# Teensy3_6Breakout.net
KiCad netlist of a schematic drawn in EAGLE
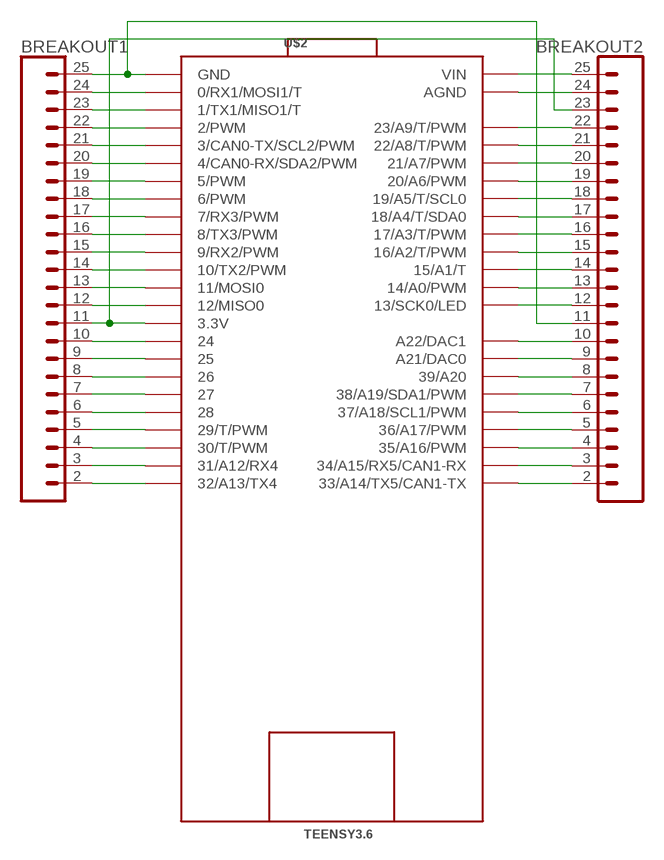
[diagram p0: schematic, sheet 1]

(export (version "E")
  (design (tool "Eeschema 10.0.6"))
  (components
    (comp (ref "BREAKOUT1")
      (value "CONN_24LONGPADS")
      (footprint "eagle-import:1X24_LONGPADS")
      (libsource (lib "eagle-import") (part "CONN_24LONGPADS"))
    )
    (comp (ref "BREAKOUT2")
      (value "CONN_24LONGPADS")
      (footprint "eagle-import:1X24_LONGPADS")
      (libsource (lib "eagle-import") (part "CONN_24LONGPADS"))
    )
    (comp (ref "U$2")
      (value "TEENSY3.6")
      (footprint "eagle-import:TEENSY3.6")
      (libsource (lib "eagle-import") (part "TEENSY3.6"))
    )
  )
  (nets
    (net (code "1") (name "Net-(BREAKOUT1-Pad6)") (class "Default")
      (node (ref "BREAKOUT1") (pin "6") (pinfunction "6_6") (pintype "passive"))
      (node (ref "U$2") (pin "28") (pinfunction "28_28") (pintype "bidirectional"))
    )
    (net (code "2") (name "Net-(BREAKOUT1-Pad7)") (class "Default")
      (node (ref "BREAKOUT1") (pin "7") (pinfunction "7_7") (pintype "passive"))
      (node (ref "U$2") (pin "27") (pinfunction "27_27") (pintype "bidirectional"))
    )
    (net (code "3") (name "Net-(BREAKOUT1-Pad8)") (class "Default")
      (node (ref "BREAKOUT1") (pin "8") (pinfunction "8_8") (pintype "passive"))
      (node (ref "U$2") (pin "26") (pinfunction "26_26") (pintype "bidirectional"))
    )
    (net (code "4") (name "Net-(BREAKOUT1-Pad9)") (class "Default")
      (node (ref "BREAKOUT1") (pin "9") (pinfunction "9_9") (pintype "passive"))
      (node (ref "U$2") (pin "25") (pinfunction "25_25") (pintype "bidirectional"))
    )
    (net (code "5") (name "Net-(BREAKOUT1-Pad10)") (class "Default")
      (node (ref "BREAKOUT1") (pin "10") (pinfunction "10_10") (pintype "passive"))
      (node (ref "U$2") (pin "24") (pinfunction "24_24") (pintype "bidirectional"))
    )
    (net (code "6") (name "Net-(BREAKOUT1-Pad11)") (class "Default")
      (node (ref "BREAKOUT1") (pin "11") (pinfunction "11_11") (pintype "passive"))
      (node (ref "BREAKOUT2") (pin "23") (pinfunction "23_23") (pintype "passive"))
      (node (ref "U$2") (pin "3.3V") (pinfunction "3.3V_3.3V") (pintype "power_in"))
      (node (ref "U$2") (pin "3.3V3") (pinfunction "3.3V_3.3V3") (pintype "power_in"))
    )
    (net (code "7") (name "Net-(BREAKOUT1-Pad25)") (class "Default")
      (node (ref "BREAKOUT1") (pin "25") (pinfunction "25_25") (pintype "passive"))
      (node (ref "BREAKOUT2") (pin "11") (pinfunction "11_11") (pintype "passive"))
      (node (ref "U$2") (pin "GND") (pinfunction "GND_GND") (pintype "power_in"))
      (node (ref "U$2") (pin "GND1") (pinfunction "GND_GND1") (pintype "power_in"))
    )
    (net (code "8") (name "Net-(BREAKOUT2-Pad8)") (class "Default")
      (node (ref "BREAKOUT2") (pin "8") (pinfunction "8_8") (pintype "passive"))
      (node (ref "U$2") (pin "39/A20") (pinfunction "39/A20_39/A20") (pintype "bidirectional"))
    )
    (net (code "9") (name "Net-(BREAKOUT2-Pad24)") (class "Default")
      (node (ref "BREAKOUT2") (pin "24") (pinfunction "24_24") (pintype "passive"))
      (node (ref "U$2") (pin "AGND") (pinfunction "AGND_AGND") (pintype "power_in"))
    )
    (net (code "10") (name "Net-(BREAKOUT2-Pad25)") (class "Default")
      (node (ref "BREAKOUT2") (pin "25") (pinfunction "25_25") (pintype "passive"))
      (node (ref "U$2") (pin "P$1") (pinfunction "VIN_P$1") (pintype "power_in"))
      (node (ref "U$2") (pin "VIN") (pinfunction "VIN_VIN") (pintype "power_in"))
    )
    (net (code "11") (name "Net-(U$2-0{slash}RX1{slash}MOSI1{slash}T)") (class "Default")
      (node (ref "BREAKOUT1") (pin "24") (pinfunction "24_24") (pintype "passive"))
      (node (ref "U$2") (pin "0") (pinfunction "0/RX1/MOSI1/T_0") (pintype "bidirectional"))
    )
    (net (code "12") (name "Net-(U$2-1{slash}TX1{slash}MISO1{slash}T)") (class "Default")
      (node (ref "BREAKOUT1") (pin "23") (pinfunction "23_23") (pintype "passive"))
      (node (ref "U$2") (pin "1") (pinfunction "1/TX1/MISO1/T_1") (pintype "bidirectional"))
    )
    (net (code "13") (name "Net-(U$2-2{slash}PWM)") (class "Default")
      (node (ref "BREAKOUT1") (pin "22") (pinfunction "22_22") (pintype "passive"))
      (node (ref "U$2") (pin "2") (pinfunction "2/PWM_2") (pintype "bidirectional"))
    )
    (net (code "14") (name "Net-(U$2-3{slash}CAN0-TX{slash}SCL2{slash}PWM)") (class "Default")
      (node (ref "BREAKOUT1") (pin "21") (pinfunction "21_21") (pintype "passive"))
      (node (ref "U$2") (pin "3") (pinfunction "3/CAN0-TX/SCL2/PWM_3") (pintype "bidirectional"))
    )
    (net (code "15") (name "Net-(U$2-4{slash}CAN0-RX{slash}SDA2{slash}PWM)") (class "Default")
      (node (ref "BREAKOUT1") (pin "20") (pinfunction "20_20") (pintype "passive"))
      (node (ref "U$2") (pin "4") (pinfunction "4/CAN0-RX/SDA2/PWM_4") (pintype "bidirectional"))
    )
    (net (code "16") (name "Net-(U$2-5{slash}PWM)") (class "Default")
      (node (ref "BREAKOUT1") (pin "19") (pinfunction "19_19") (pintype "passive"))
      (node (ref "U$2") (pin "5") (pinfunction "5/PWM_5") (pintype "bidirectional"))
    )
    (net (code "17") (name "Net-(U$2-6{slash}PWM)") (class "Default")
      (node (ref "BREAKOUT1") (pin "18") (pinfunction "18_18") (pintype "passive"))
      (node (ref "U$2") (pin "6") (pinfunction "6/PWM_6") (pintype "bidirectional"))
    )
    (net (code "18") (name "Net-(U$2-7{slash}RX3{slash}PWM)") (class "Default")
      (node (ref "BREAKOUT1") (pin "17") (pinfunction "17_17") (pintype "passive"))
      (node (ref "U$2") (pin "7") (pinfunction "7/RX3/PWM_7") (pintype "bidirectional"))
    )
    (net (code "19") (name "Net-(U$2-8{slash}TX3{slash}PWM)") (class "Default")
      (node (ref "BREAKOUT1") (pin "16") (pinfunction "16_16") (pintype "passive"))
      (node (ref "U$2") (pin "8") (pinfunction "8/TX3/PWM_8") (pintype "bidirectional"))
    )
    (net (code "20") (name "Net-(U$2-9{slash}RX2{slash}PWM)") (class "Default")
      (node (ref "BREAKOUT1") (pin "15") (pinfunction "15_15") (pintype "passive"))
      (node (ref "U$2") (pin "9") (pinfunction "9/RX2/PWM_9") (pintype "bidirectional"))
    )
    (net (code "21") (name "Net-(U$2-10{slash}TX2{slash}PWM)") (class "Default")
      (node (ref "BREAKOUT1") (pin "14") (pinfunction "14_14") (pintype "passive"))
      (node (ref "U$2") (pin "10") (pinfunction "10/TX2/PWM_10") (pintype "bidirectional"))
    )
    (net (code "22") (name "Net-(U$2-11{slash}MOSI0)") (class "Default")
      (node (ref "BREAKOUT1") (pin "13") (pinfunction "13_13") (pintype "passive"))
      (node (ref "U$2") (pin "11") (pinfunction "11/MOSI0_11") (pintype "bidirectional"))
    )
    (net (code "23") (name "Net-(U$2-12{slash}MISO0)") (class "Default")
      (node (ref "BREAKOUT1") (pin "12") (pinfunction "12_12") (pintype "passive"))
      (node (ref "U$2") (pin "12") (pinfunction "12/MISO0_12") (pintype "bidirectional"))
    )
    (net (code "24") (name "Net-(U$2-13{slash}SCK0{slash}LED)") (class "Default")
      (node (ref "BREAKOUT2") (pin "12") (pinfunction "12_12") (pintype "passive"))
      (node (ref "U$2") (pin "13") (pinfunction "13/SCK0/LED_13") (pintype "bidirectional"))
    )
    (net (code "25") (name "Net-(U$2-14{slash}A0{slash}PWM)") (class "Default")
      (node (ref "BREAKOUT2") (pin "13") (pinfunction "13_13") (pintype "passive"))
      (node (ref "U$2") (pin "14/A0") (pinfunction "14/A0/PWM_14/A0") (pintype "bidirectional"))
    )
    (net (code "26") (name "Net-(U$2-15{slash}A1{slash}T)") (class "Default")
      (node (ref "BREAKOUT2") (pin "14") (pinfunction "14_14") (pintype "passive"))
      (node (ref "U$2") (pin "15/A1") (pinfunction "15/A1/T_15/A1") (pintype "bidirectional"))
    )
    (net (code "27") (name "Net-(U$2-16{slash}A2{slash}T{slash}PWM)") (class "Default")
      (node (ref "BREAKOUT2") (pin "15") (pinfunction "15_15") (pintype "passive"))
      (node (ref "U$2") (pin "16/A2") (pinfunction "16/A2/T/PWM_16/A2") (pintype "bidirectional"))
    )
    (net (code "28") (name "Net-(U$2-17{slash}A3{slash}T{slash}PWM)") (class "Default")
      (node (ref "BREAKOUT2") (pin "16") (pinfunction "16_16") (pintype "passive"))
      (node (ref "U$2") (pin "17/A3") (pinfunction "17/A3/T/PWM_17/A3") (pintype "bidirectional"))
    )
    (net (code "29") (name "Net-(U$2-18{slash}A4{slash}T{slash}SDA0)") (class "Default")
      (node (ref "BREAKOUT2") (pin "17") (pinfunction "17_17") (pintype "passive"))
      (node (ref "U$2") (pin "18/A4") (pinfunction "18/A4/T/SDA0_18/A4") (pintype "bidirectional"))
    )
    (net (code "30") (name "Net-(U$2-19{slash}A5{slash}T{slash}SCL0)") (class "Default")
      (node (ref "BREAKOUT2") (pin "18") (pinfunction "18_18") (pintype "passive"))
      (node (ref "U$2") (pin "19/A5") (pinfunction "19/A5/T/SCL0_19/A5") (pintype "bidirectional"))
    )
    (net (code "31") (name "Net-(U$2-20{slash}A6{slash}PWM)") (class "Default")
      (node (ref "BREAKOUT2") (pin "19") (pinfunction "19_19") (pintype "passive"))
      (node (ref "U$2") (pin "20/A6") (pinfunction "20/A6/PWM_20/A6") (pintype "bidirectional"))
    )
    (net (code "32") (name "Net-(U$2-21{slash}A7{slash}PWM)") (class "Default")
      (node (ref "BREAKOUT2") (pin "20") (pinfunction "20_20") (pintype "passive"))
      (node (ref "U$2") (pin "21/A7") (pinfunction "21/A7/PWM_21/A7") (pintype "bidirectional"))
    )
    (net (code "33") (name "Net-(U$2-22{slash}A8{slash}T{slash}PWM)") (class "Default")
      (node (ref "BREAKOUT2") (pin "21") (pinfunction "21_21") (pintype "passive"))
      (node (ref "U$2") (pin "22/A8") (pinfunction "22/A8/T/PWM_22/A8") (pintype "bidirectional"))
    )
    (net (code "34") (name "Net-(U$2-23{slash}A9{slash}T{slash}PWM)") (class "Default")
      (node (ref "BREAKOUT2") (pin "22") (pinfunction "22_22") (pintype "passive"))
      (node (ref "U$2") (pin "23/A9") (pinfunction "23/A9/T/PWM_23/A9") (pintype "bidirectional"))
    )
    (net (code "35") (name "Net-(U$2-29{slash}T{slash}PWM)") (class "Default")
      (node (ref "BREAKOUT1") (pin "5") (pinfunction "5_5") (pintype "passive"))
      (node (ref "U$2") (pin "29") (pinfunction "29/T/PWM_29") (pintype "bidirectional"))
    )
    (net (code "36") (name "Net-(U$2-30{slash}T{slash}PWM)") (class "Default")
      (node (ref "BREAKOUT1") (pin "4") (pinfunction "4_4") (pintype "passive"))
      (node (ref "U$2") (pin "30") (pinfunction "30/T/PWM_30") (pintype "bidirectional"))
    )
    (net (code "37") (name "Net-(U$2-31{slash}A12{slash}RX4)") (class "Default")
      (node (ref "BREAKOUT1") (pin "3") (pinfunction "3_3") (pintype "passive"))
      (node (ref "U$2") (pin "31/A12") (pinfunction "31/A12/RX4_31/A12") (pintype "bidirectional"))
    )
    (net (code "38") (name "Net-(U$2-32{slash}A13{slash}TX4)") (class "Default")
      (node (ref "BREAKOUT1") (pin "2") (pinfunction "2_2") (pintype "passive"))
      (node (ref "U$2") (pin "32/A13") (pinfunction "32/A13/TX4_32/A13") (pintype "bidirectional"))
    )
    (net (code "39") (name "Net-(U$2-33{slash}A14{slash}TX5{slash}CAN1-TX)") (class "Default")
      (node (ref "BREAKOUT2") (pin "2") (pinfunction "2_2") (pintype "passive"))
      (node (ref "U$2") (pin "33/A14") (pinfunction "33/A14/TX5/CAN1-TX_33/A14") (pintype "bidirectional"))
    )
    (net (code "40") (name "Net-(U$2-34{slash}A15{slash}RX5{slash}CAN1-RX)") (class "Default")
      (node (ref "BREAKOUT2") (pin "3") (pinfunction "3_3") (pintype "passive"))
      (node (ref "U$2") (pin "34/A15") (pinfunction "34/A15/RX5/CAN1-RX_34/A15") (pintype "bidirectional"))
    )
    (net (code "41") (name "Net-(U$2-35{slash}A16{slash}PWM)") (class "Default")
      (node (ref "BREAKOUT2") (pin "4") (pinfunction "4_4") (pintype "passive"))
      (node (ref "U$2") (pin "35/A16") (pinfunction "35/A16/PWM_35/A16") (pintype "bidirectional"))
    )
    (net (code "42") (name "Net-(U$2-36{slash}A17{slash}PWM)") (class "Default")
      (node (ref "BREAKOUT2") (pin "5") (pinfunction "5_5") (pintype "passive"))
      (node (ref "U$2") (pin "36/A17") (pinfunction "36/A17/PWM_36/A17") (pintype "bidirectional"))
    )
    (net (code "43") (name "Net-(U$2-37{slash}A18{slash}SCL1{slash}PWM)") (class "Default")
      (node (ref "BREAKOUT2") (pin "6") (pinfunction "6_6") (pintype "passive"))
      (node (ref "U$2") (pin "37/A18") (pinfunction "37/A18/SCL1/PWM_37/A18") (pintype "bidirectional"))
    )
    (net (code "44") (name "Net-(U$2-38{slash}A19{slash}SDA1{slash}PWM)") (class "Default")
      (node (ref "BREAKOUT2") (pin "7") (pinfunction "7_7") (pintype "passive"))
      (node (ref "U$2") (pin "38/A19") (pinfunction "38/A19/SDA1/PWM_38/A19") (pintype "bidirectional"))
    )
    (net (code "45") (name "Net-(U$2-A21{slash}DAC0)") (class "Default")
      (node (ref "BREAKOUT2") (pin "9") (pinfunction "9_9") (pintype "passive"))
      (node (ref "U$2") (pin "A21") (pinfunction "A21/DAC0_A21") (pintype "bidirectional"))
    )
    (net (code "46") (name "Net-(U$2-A22{slash}DAC1)") (class "Default")
      (node (ref "BREAKOUT2") (pin "10") (pinfunction "10_10") (pintype "passive"))
      (node (ref "U$2") (pin "A22") (pinfunction "A22/DAC1_A22") (pintype "bidirectional"))
    )
  )
)
